# HDMI_MIPI-DSI_EDP.net
KiCad netlist of a schematic drawn in Altium Designer
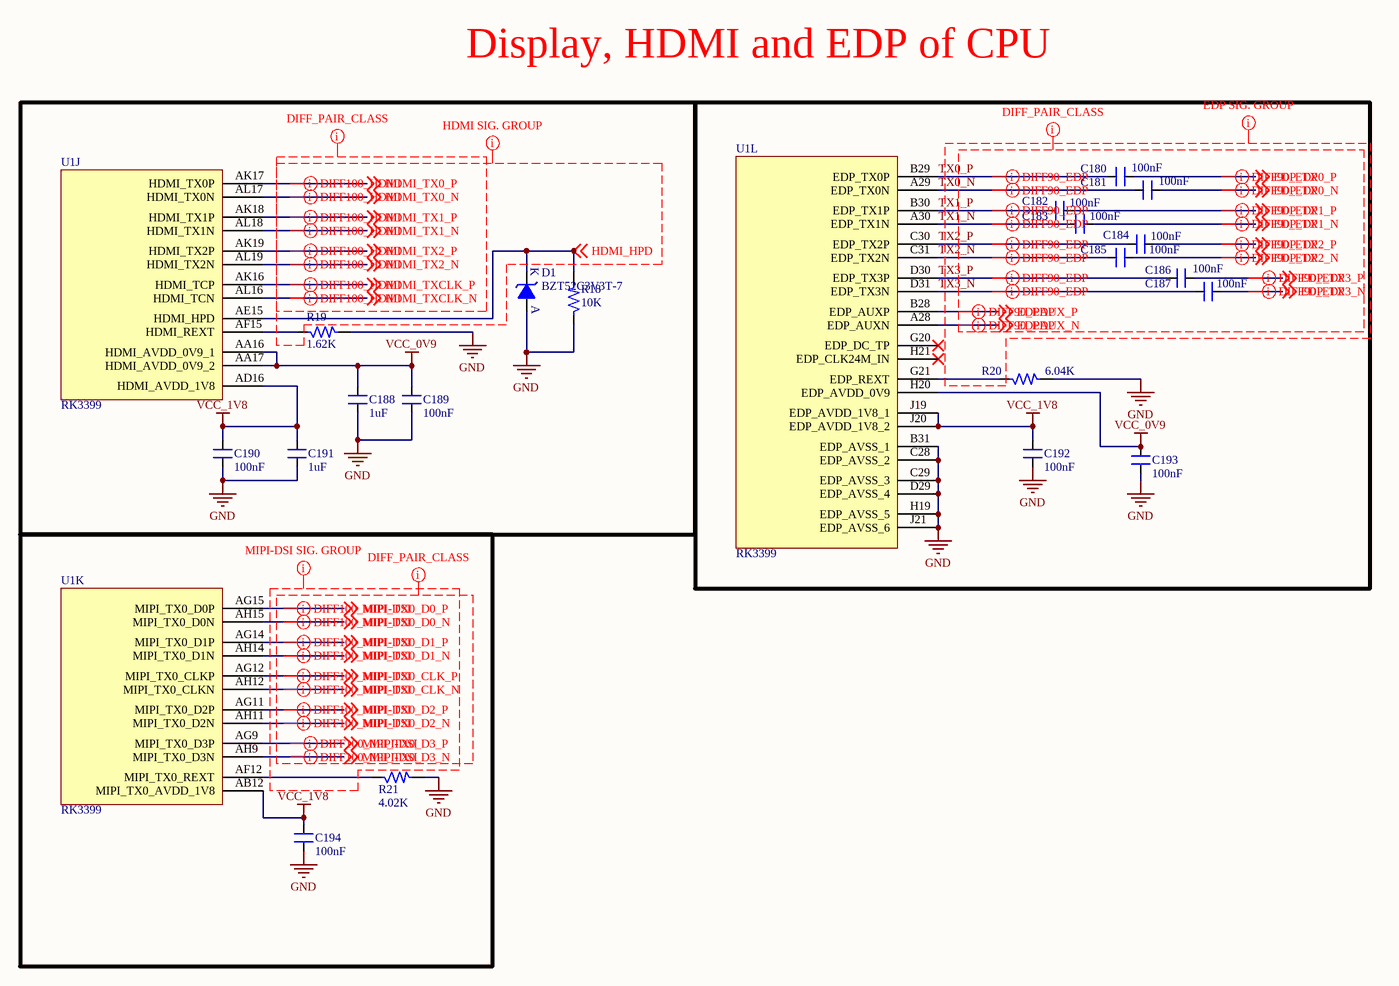
[diagram p0: HDMI_MIPI-DSI_EDP.SchDoc]

(export (version "E")
  (design (tool "Eeschema 10.0.6"))
  (components
    (comp (ref "C180")
      (value "100nF")
      (footprint "CAP_0201")
      (description "0.1µF ±10% 25V Ceramic Capacitor X5R 0201 (0603 Metric)")
      (fields
        (field (name "MANUFACTURER") "TDK Corporation")
        (field (name "MANUFACTURER PART NUMBER") "C0603X5R1E104K030BB")
      )
      (libsource (lib "RK3399 _Module_Intlib") (part "CAP_100nF-25V-10%-0201"))
    )
    (comp (ref "C181")
      (value "100nF")
      (footprint "CAP_0201")
      (description "0.1µF ±10% 25V Ceramic Capacitor X5R 0201 (0603 Metric)")
      (fields
        (field (name "MANUFACTURER") "TDK Corporation")
        (field (name "MANUFACTURER PART NUMBER") "C0603X5R1E104K030BB")
      )
      (libsource (lib "RK3399 _Module_Intlib") (part "CAP_100nF-25V-10%-0201"))
    )
    (comp (ref "C182")
      (value "100nF")
      (footprint "CAP_0201")
      (description "0.1µF ±10% 25V Ceramic Capacitor X5R 0201 (0603 Metric)")
      (fields
        (field (name "MANUFACTURER") "TDK Corporation")
        (field (name "MANUFACTURER PART NUMBER") "C0603X5R1E104K030BB")
      )
      (libsource (lib "RK3399 _Module_Intlib") (part "CAP_100nF-25V-10%-0201"))
    )
    (comp (ref "C183")
      (value "100nF")
      (footprint "CAP_0201")
      (description "0.1µF ±10% 25V Ceramic Capacitor X5R 0201 (0603 Metric)")
      (fields
        (field (name "MANUFACTURER") "TDK Corporation")
        (field (name "MANUFACTURER PART NUMBER") "C0603X5R1E104K030BB")
      )
      (libsource (lib "RK3399 _Module_Intlib") (part "CAP_100nF-25V-10%-0201"))
    )
    (comp (ref "C184")
      (value "100nF")
      (footprint "CAP_0201")
      (description "0.1µF ±10% 25V Ceramic Capacitor X5R 0201 (0603 Metric)")
      (fields
        (field (name "MANUFACTURER") "TDK Corporation")
        (field (name "MANUFACTURER PART NUMBER") "C0603X5R1E104K030BB")
      )
      (libsource (lib "RK3399 _Module_Intlib") (part "CAP_100nF-25V-10%-0201"))
    )
    (comp (ref "C185")
      (value "100nF")
      (footprint "CAP_0201")
      (description "0.1µF ±10% 25V Ceramic Capacitor X5R 0201 (0603 Metric)")
      (fields
        (field (name "MANUFACTURER") "TDK Corporation")
        (field (name "MANUFACTURER PART NUMBER") "C0603X5R1E104K030BB")
      )
      (libsource (lib "RK3399 _Module_Intlib") (part "CAP_100nF-25V-10%-0201"))
    )
    (comp (ref "C186")
      (value "100nF")
      (footprint "CAP_0201")
      (description "0.1µF ±10% 25V Ceramic Capacitor X5R 0201 (0603 Metric)")
      (fields
        (field (name "MANUFACTURER") "TDK Corporation")
        (field (name "MANUFACTURER PART NUMBER") "C0603X5R1E104K030BB")
      )
      (libsource (lib "RK3399 _Module_Intlib") (part "CAP_100nF-25V-10%-0201"))
    )
    (comp (ref "C187")
      (value "100nF")
      (footprint "CAP_0201")
      (description "0.1µF ±10% 25V Ceramic Capacitor X5R 0201 (0603 Metric)")
      (fields
        (field (name "MANUFACTURER") "TDK Corporation")
        (field (name "MANUFACTURER PART NUMBER") "C0603X5R1E104K030BB")
      )
      (libsource (lib "RK3399 _Module_Intlib") (part "CAP_100nF-25V-10%-0201"))
    )
    (comp (ref "C188")
      (value "1uF")
      (footprint "CAP_0201")
      (description "1µF ±20% 16V Ceramic Capacitor X5R 0201 (0603 Metric)")
      (fields
        (field (name "MANUFACTURER") "Samsung Electro-Mechanics")
        (field (name "MANUFACTURER PART NUMBER") "CL03A105MO3NRNH")
      )
      (libsource (lib "RK3399 _Module_Intlib") (part "CAP_1uF-16V-10%-0201"))
    )
    (comp (ref "C189")
      (value "100nF")
      (footprint "CAP_0201")
      (description "0.1µF ±10% 25V Ceramic Capacitor X5R 0201 (0603 Metric)")
      (fields
        (field (name "MANUFACTURER") "TDK Corporation")
        (field (name "MANUFACTURER PART NUMBER") "C0603X5R1E104K030BB")
      )
      (libsource (lib "RK3399 _Module_Intlib") (part "CAP_100nF-25V-10%-0201"))
    )
    (comp (ref "C190")
      (value "100nF")
      (footprint "CAP_0201")
      (description "0.1µF ±10% 25V Ceramic Capacitor X5R 0201 (0603 Metric)")
      (fields
        (field (name "MANUFACTURER") "TDK Corporation")
        (field (name "MANUFACTURER PART NUMBER") "C0603X5R1E104K030BB")
      )
      (libsource (lib "RK3399 _Module_Intlib") (part "CAP_100nF-25V-10%-0201"))
    )
    (comp (ref "C191")
      (value "1uF")
      (footprint "CAP_0201")
      (description "1µF ±20% 16V Ceramic Capacitor X5R 0201 (0603 Metric)")
      (fields
        (field (name "MANUFACTURER") "Samsung Electro-Mechanics")
        (field (name "MANUFACTURER PART NUMBER") "CL03A105MO3NRNH")
      )
      (libsource (lib "RK3399 _Module_Intlib") (part "CAP_1uF-16V-10%-0201"))
    )
    (comp (ref "C192")
      (value "100nF")
      (footprint "CAP_0201")
      (description "0.1µF ±10% 25V Ceramic Capacitor X5R 0201 (0603 Metric)")
      (fields
        (field (name "MANUFACTURER") "TDK Corporation")
        (field (name "MANUFACTURER PART NUMBER") "C0603X5R1E104K030BB")
      )
      (libsource (lib "RK3399 _Module_Intlib") (part "CAP_100nF-25V-10%-0201"))
    )
    (comp (ref "C193")
      (value "100nF")
      (footprint "CAP_0201")
      (description "0.1µF ±10% 25V Ceramic Capacitor X5R 0201 (0603 Metric)")
      (fields
        (field (name "MANUFACTURER") "TDK Corporation")
        (field (name "MANUFACTURER PART NUMBER") "C0603X5R1E104K030BB")
      )
      (libsource (lib "RK3399 _Module_Intlib") (part "CAP_100nF-25V-10%-0201"))
    )
    (comp (ref "C194")
      (value "100nF")
      (footprint "CAP_0201")
      (description "0.1µF ±10% 25V Ceramic Capacitor X5R 0201 (0603 Metric)")
      (fields
        (field (name "MANUFACTURER") "TDK Corporation")
        (field (name "MANUFACTURER PART NUMBER") "C0603X5R1E104K030BB")
      )
      (libsource (lib "RK3399 _Module_Intlib") (part "CAP_100nF-25V-10%-0201"))
    )
    (comp (ref "D1")
      (value "BZT52C3V3T-7")
      (footprint "DIO_SOD523")
      (description "Zener Diode 3.3V 300mW ±6% Surface Mount SOD-523")
      (fields (field (name "MANUFACTURER") "Diodes Incorporated"))
      (libsource (lib "RK3399 _Module_Schlib") (part "DIO-Z_3.3V-300mW-SOD-523"))
    )
    (comp (ref "R18")
      (value "10K")
      (footprint "RES_0201")
      (description "10 kOhms ±1% 0.05W, 1/20W Chip Resistor 0201 (0603 Metric) Thick Film")
      (fields
        (field (name "MANUFACTURER") "Stackpole Electronics Inc")
        (field (name "MANUFACTURER PART NUMBER") "RMCF0201FT10K0")
      )
      (libsource (lib "RK3399 _Module_Intlib") (part "RES_10K-0.05W-1%-0201"))
    )
    (comp (ref "R19")
      (value "1.62K")
      (footprint "RES_0201")
      (description "1.62 kOhms ±1% 0.05W, 1/20W Chip Resistor 0201 (0603 Metric) Automotive AEC-Q200 Thick Film")
      (fields
        (field (name "MANUFACTURER") "Panasonic Electronic Components")
        (field (name "MANUFACTURER PART NUMBER") "ERJ-1GNF1621C")
      )
      (libsource (lib "RK3399 _Module_Intlib") (part "RES_1.62K-0.05W-1%-0201"))
    )
    (comp (ref "R20")
      (value "6.04K")
      (footprint "RES_0201")
      (description "6.04 kOhms ±1% 0.05W, 1/20W Chip Resistor 0201 (0603 Metric) Thick Film")
      (fields
        (field (name "MANUFACTURER") "Panasonic Electronic Components")
        (field (name "MANUFACTURER PART NUMBER") "ERJ-1GEF6041C")
      )
      (libsource (lib "RK3399 _Module_Intlib") (part "RES_6.04K-0.05W-1%-0201"))
    )
    (comp (ref "R21")
      (value "4.02K")
      (footprint "RES_0201")
      (description "4.02 kOhms ±1% 0.05W, 1/20W Chip Resistor 0201 (0603 Metric) Thick Film")
      (fields
        (field (name "MANUFACTURER") "Yageo")
        (field (name "MANUFACTURER PART NUMBER") "RC0201FR-074K02L")
      )
      (libsource (lib "RK3399 _Module_Intlib") (part "RES_4.02K-0.05W-1%-0201"))
    )
    (comp (ref "U1")
      (value "RK3399")
      (footprint "FBGA828_23_826X826")
      (description "RK3399 is a low power, high performance processor for computing, personal mobile.")
      (fields (field (name "MANUFACTURER") "Rockchip"))
      (libsource (lib "RK3399 _Module_Schlib") (part "IC_RK3399-FCBGA828"))
    )
  )
  (nets
    (net (code "1") (name "/TX0_N") (class "Default")
      (node (ref "C181") (pin "2") (pinfunction "2_2") (pintype "passive"))
      (node (ref "U1") (pin "A29") (pinfunction "EDP_TX0N_A29") (pintype "passive"))
    )
    (net (code "2") (name "/TX0_P") (class "Default")
      (node (ref "C180") (pin "2") (pinfunction "2_2") (pintype "passive"))
      (node (ref "U1") (pin "B29") (pinfunction "EDP_TX0P_B29") (pintype "passive"))
    )
    (net (code "3") (name "/TX1_N") (class "Default")
      (node (ref "C183") (pin "2") (pinfunction "2_2") (pintype "passive"))
      (node (ref "U1") (pin "A30") (pinfunction "EDP_TX1N_A30") (pintype "passive"))
    )
    (net (code "4") (name "/TX1_P") (class "Default")
      (node (ref "C182") (pin "2") (pinfunction "2_2") (pintype "passive"))
      (node (ref "U1") (pin "B30") (pinfunction "EDP_TX1P_B30") (pintype "passive"))
    )
    (net (code "5") (name "/TX2_N") (class "Default")
      (node (ref "C185") (pin "2") (pinfunction "2_2") (pintype "passive"))
      (node (ref "U1") (pin "C31") (pinfunction "EDP_TX2N_C31") (pintype "passive"))
    )
    (net (code "6") (name "/TX2_P") (class "Default")
      (node (ref "C184") (pin "2") (pinfunction "2_2") (pintype "passive"))
      (node (ref "U1") (pin "C30") (pinfunction "EDP_TX2P_C30") (pintype "passive"))
    )
    (net (code "7") (name "/TX3_N") (class "Default")
      (node (ref "C187") (pin "2") (pinfunction "2_2") (pintype "passive"))
      (node (ref "U1") (pin "D31") (pinfunction "EDP_TX3N_D31") (pintype "passive"))
    )
    (net (code "8") (name "/TX3_P") (class "Default")
      (node (ref "C186") (pin "2") (pinfunction "2_2") (pintype "passive"))
      (node (ref "U1") (pin "D30") (pinfunction "EDP_TX3P_D30") (pintype "passive"))
    )
    (net (code "9") (name "EDPAUX_N") (class "Default")
      (node (ref "U1") (pin "A28") (pinfunction "EDP_AUXN_A28") (pintype "passive"))
    )
    (net (code "10") (name "EDPAUX_P") (class "Default")
      (node (ref "U1") (pin "B28") (pinfunction "EDP_AUXP_B28") (pintype "passive"))
    )
    (net (code "11") (name "EDP_TX0_N") (class "Default")
      (node (ref "C181") (pin "1") (pinfunction "1_1") (pintype "passive"))
    )
    (net (code "12") (name "EDP_TX0_P") (class "Default")
      (node (ref "C180") (pin "1") (pinfunction "1_1") (pintype "passive"))
    )
    (net (code "13") (name "EDP_TX1_N") (class "Default")
      (node (ref "C183") (pin "1") (pinfunction "1_1") (pintype "passive"))
    )
    (net (code "14") (name "EDP_TX1_P") (class "Default")
      (node (ref "C182") (pin "1") (pinfunction "1_1") (pintype "passive"))
    )
    (net (code "15") (name "EDP_TX2_N") (class "Default")
      (node (ref "C185") (pin "1") (pinfunction "1_1") (pintype "passive"))
    )
    (net (code "16") (name "EDP_TX2_P") (class "Default")
      (node (ref "C184") (pin "1") (pinfunction "1_1") (pintype "passive"))
    )
    (net (code "17") (name "EDP_TX3_N") (class "Default")
      (node (ref "C187") (pin "1") (pinfunction "1_1") (pintype "passive"))
    )
    (net (code "18") (name "EDP_TX3_P") (class "Default")
      (node (ref "C186") (pin "1") (pinfunction "1_1") (pintype "passive"))
    )
    (net (code "19") (name "GND") (class "Default")
      (node (ref "C188") (pin "1") (pinfunction "1_1") (pintype "passive"))
      (node (ref "C189") (pin "1") (pinfunction "1_1") (pintype "passive"))
      (node (ref "C190") (pin "1") (pinfunction "1_1") (pintype "passive"))
      (node (ref "C191") (pin "1") (pinfunction "1_1") (pintype "passive"))
      (node (ref "C192") (pin "2") (pinfunction "2_2") (pintype "passive"))
      (node (ref "C193") (pin "1") (pinfunction "1_1") (pintype "passive"))
      (node (ref "C194") (pin "1") (pinfunction "1_1") (pintype "passive"))
      (node (ref "D1") (pin "A") (pinfunction "A_A") (pintype "passive"))
      (node (ref "R18") (pin "1") (pinfunction "1_1") (pintype "passive"))
      (node (ref "R19") (pin "2") (pinfunction "2_2") (pintype "passive"))
      (node (ref "R20") (pin "2") (pinfunction "2_2") (pintype "passive"))
      (node (ref "R21") (pin "2") (pinfunction "2_2") (pintype "passive"))
      (node (ref "U1") (pin "B31") (pinfunction "EDP_AVSS_1_B31") (pintype "passive"))
      (node (ref "U1") (pin "C28") (pinfunction "EDP_AVSS_2_C28") (pintype "passive"))
      (node (ref "U1") (pin "C29") (pinfunction "EDP_AVSS_3_C29") (pintype "passive"))
      (node (ref "U1") (pin "D29") (pinfunction "EDP_AVSS_4_D29") (pintype "passive"))
      (node (ref "U1") (pin "H19") (pinfunction "EDP_AVSS_5_H19") (pintype "passive"))
      (node (ref "U1") (pin "J21") (pinfunction "EDP_AVSS_6_J21") (pintype "passive"))
    )
    (net (code "20") (name "HDMI_HPD") (class "Default")
      (node (ref "D1") (pin "K") (pinfunction "K_K") (pintype "passive"))
      (node (ref "R18") (pin "2") (pinfunction "2_2") (pintype "passive"))
      (node (ref "U1") (pin "AE15") (pinfunction "HDMI_HPD_AE15") (pintype "passive"))
    )
    (net (code "21") (name "HDMI_TX0_N") (class "Default")
      (node (ref "U1") (pin "AL17") (pinfunction "HDMI_TX0N_AL17") (pintype "passive"))
    )
    (net (code "22") (name "HDMI_TX0_P") (class "Default")
      (node (ref "U1") (pin "AK17") (pinfunction "HDMI_TX0P_AK17") (pintype "passive"))
    )
    (net (code "23") (name "HDMI_TX1_N") (class "Default")
      (node (ref "U1") (pin "AL18") (pinfunction "HDMI_TX1N_AL18") (pintype "passive"))
    )
    (net (code "24") (name "HDMI_TX1_P") (class "Default")
      (node (ref "U1") (pin "AK18") (pinfunction "HDMI_TX1P_AK18") (pintype "passive"))
    )
    (net (code "25") (name "HDMI_TX2_N") (class "Default")
      (node (ref "U1") (pin "AL19") (pinfunction "HDMI_TX2N_AL19") (pintype "passive"))
    )
    (net (code "26") (name "HDMI_TX2_P") (class "Default")
      (node (ref "U1") (pin "AK19") (pinfunction "HDMI_TX2P_AK19") (pintype "passive"))
    )
    (net (code "27") (name "HDMI_TXCLK_N") (class "Default")
      (node (ref "U1") (pin "AL16") (pinfunction "HDMI_TCN_AL16") (pintype "passive"))
    )
    (net (code "28") (name "HDMI_TXCLK_P") (class "Default")
      (node (ref "U1") (pin "AK16") (pinfunction "HDMI_TCP_AK16") (pintype "passive"))
    )
    (net (code "29") (name "MIPI_TX0_CLK_N") (class "Default")
      (node (ref "U1") (pin "AH12") (pinfunction "MIPI_TX0_CLKN_AH12") (pintype "passive"))
    )
    (net (code "30") (name "MIPI_TX0_CLK_P") (class "Default")
      (node (ref "U1") (pin "AG12") (pinfunction "MIPI_TX0_CLKP_AG12") (pintype "passive"))
    )
    (net (code "31") (name "MIPI_TX0_D0_N") (class "Default")
      (node (ref "U1") (pin "AH15") (pinfunction "MIPI_TX0_D0N_AH15") (pintype "passive"))
    )
    (net (code "32") (name "MIPI_TX0_D0_P") (class "Default")
      (node (ref "U1") (pin "AG15") (pinfunction "MIPI_TX0_D0P_AG15") (pintype "passive"))
    )
    (net (code "33") (name "MIPI_TX0_D1_N") (class "Default")
      (node (ref "U1") (pin "AH14") (pinfunction "MIPI_TX0_D1N_AH14") (pintype "passive"))
    )
    (net (code "34") (name "MIPI_TX0_D1_P") (class "Default")
      (node (ref "U1") (pin "AG14") (pinfunction "MIPI_TX0_D1P_AG14") (pintype "passive"))
    )
    (net (code "35") (name "MIPI_TX0_D2_N") (class "Default")
      (node (ref "U1") (pin "AH11") (pinfunction "MIPI_TX0_D2N_AH11") (pintype "passive"))
    )
    (net (code "36") (name "MIPI_TX0_D2_P") (class "Default")
      (node (ref "U1") (pin "AG11") (pinfunction "MIPI_TX0_D2P_AG11") (pintype "passive"))
    )
    (net (code "37") (name "MIPI_TX0_D3_N") (class "Default")
      (node (ref "U1") (pin "AH9") (pinfunction "MIPI_TX0_D3N_AH9") (pintype "passive"))
    )
    (net (code "38") (name "MIPI_TX0_D3_P") (class "Default")
      (node (ref "U1") (pin "AG9") (pinfunction "MIPI_TX0_D3P_AG9") (pintype "passive"))
    )
    (net (code "39") (name "Net-(U1J-HDMI_REXT)") (class "Default")
      (node (ref "R19") (pin "1") (pinfunction "1_1") (pintype "passive"))
      (node (ref "U1") (pin "AF15") (pinfunction "HDMI_REXT_AF15") (pintype "passive"))
    )
    (net (code "40") (name "Net-(U1K-MIPI_TX0_REXT)") (class "Default")
      (node (ref "R21") (pin "1") (pinfunction "1_1") (pintype "passive"))
      (node (ref "U1") (pin "AF12") (pinfunction "MIPI_TX0_REXT_AF12") (pintype "passive"))
    )
    (net (code "41") (name "Net-(U1L-EDP_REXT)") (class "Default")
      (node (ref "R20") (pin "1") (pinfunction "1_1") (pintype "passive"))
      (node (ref "U1") (pin "G21") (pinfunction "EDP_REXT_G21") (pintype "passive"))
    )
    (net (code "42") (name "VCC_0V9") (class "Default")
      (node (ref "C188") (pin "2") (pinfunction "2_2") (pintype "passive"))
      (node (ref "C189") (pin "2") (pinfunction "2_2") (pintype "passive"))
      (node (ref "C193") (pin "2") (pinfunction "2_2") (pintype "passive"))
      (node (ref "U1") (pin "AA16") (pinfunction "HDMI_AVDD_0V9_1_AA16") (pintype "passive"))
      (node (ref "U1") (pin "AA17") (pinfunction "HDMI_AVDD_0V9_2_AA17") (pintype "passive"))
      (node (ref "U1") (pin "H20") (pinfunction "EDP_AVDD_0V9_H20") (pintype "passive"))
    )
    (net (code "43") (name "VCC_1V8") (class "Default")
      (node (ref "C190") (pin "2") (pinfunction "2_2") (pintype "passive"))
      (node (ref "C191") (pin "2") (pinfunction "2_2") (pintype "passive"))
      (node (ref "C192") (pin "1") (pinfunction "1_1") (pintype "passive"))
      (node (ref "C194") (pin "2") (pinfunction "2_2") (pintype "passive"))
      (node (ref "U1") (pin "AB12") (pinfunction "MIPI_TX0_AVDD_1V8_AB12") (pintype "passive"))
      (node (ref "U1") (pin "AD16") (pinfunction "HDMI_AVDD_1V8_AD16") (pintype "passive"))
      (node (ref "U1") (pin "J19") (pinfunction "EDP_AVDD_1V8_1_J19") (pintype "passive"))
      (node (ref "U1") (pin "J20") (pinfunction "EDP_AVDD_1V8_2_J20") (pintype "passive"))
    )
    (net (code "44") (name "unconnected-(U1L-EDP_CLK24M_IN-PadH21)") (class "Default")
      (node (ref "U1") (pin "H21") (pinfunction "EDP_CLK24M_IN_H21") (pintype "passive+no_connect"))
    )
    (net (code "45") (name "unconnected-(U1L-EDP_DC_TP-PadG20)") (class "Default")
      (node (ref "U1") (pin "G20") (pinfunction "EDP_DC_TP_G20") (pintype "passive+no_connect"))
    )
  )
)
